# PROJECT-TSC_v61.net
KiCad netlist of a schematic drawn in EAGLE
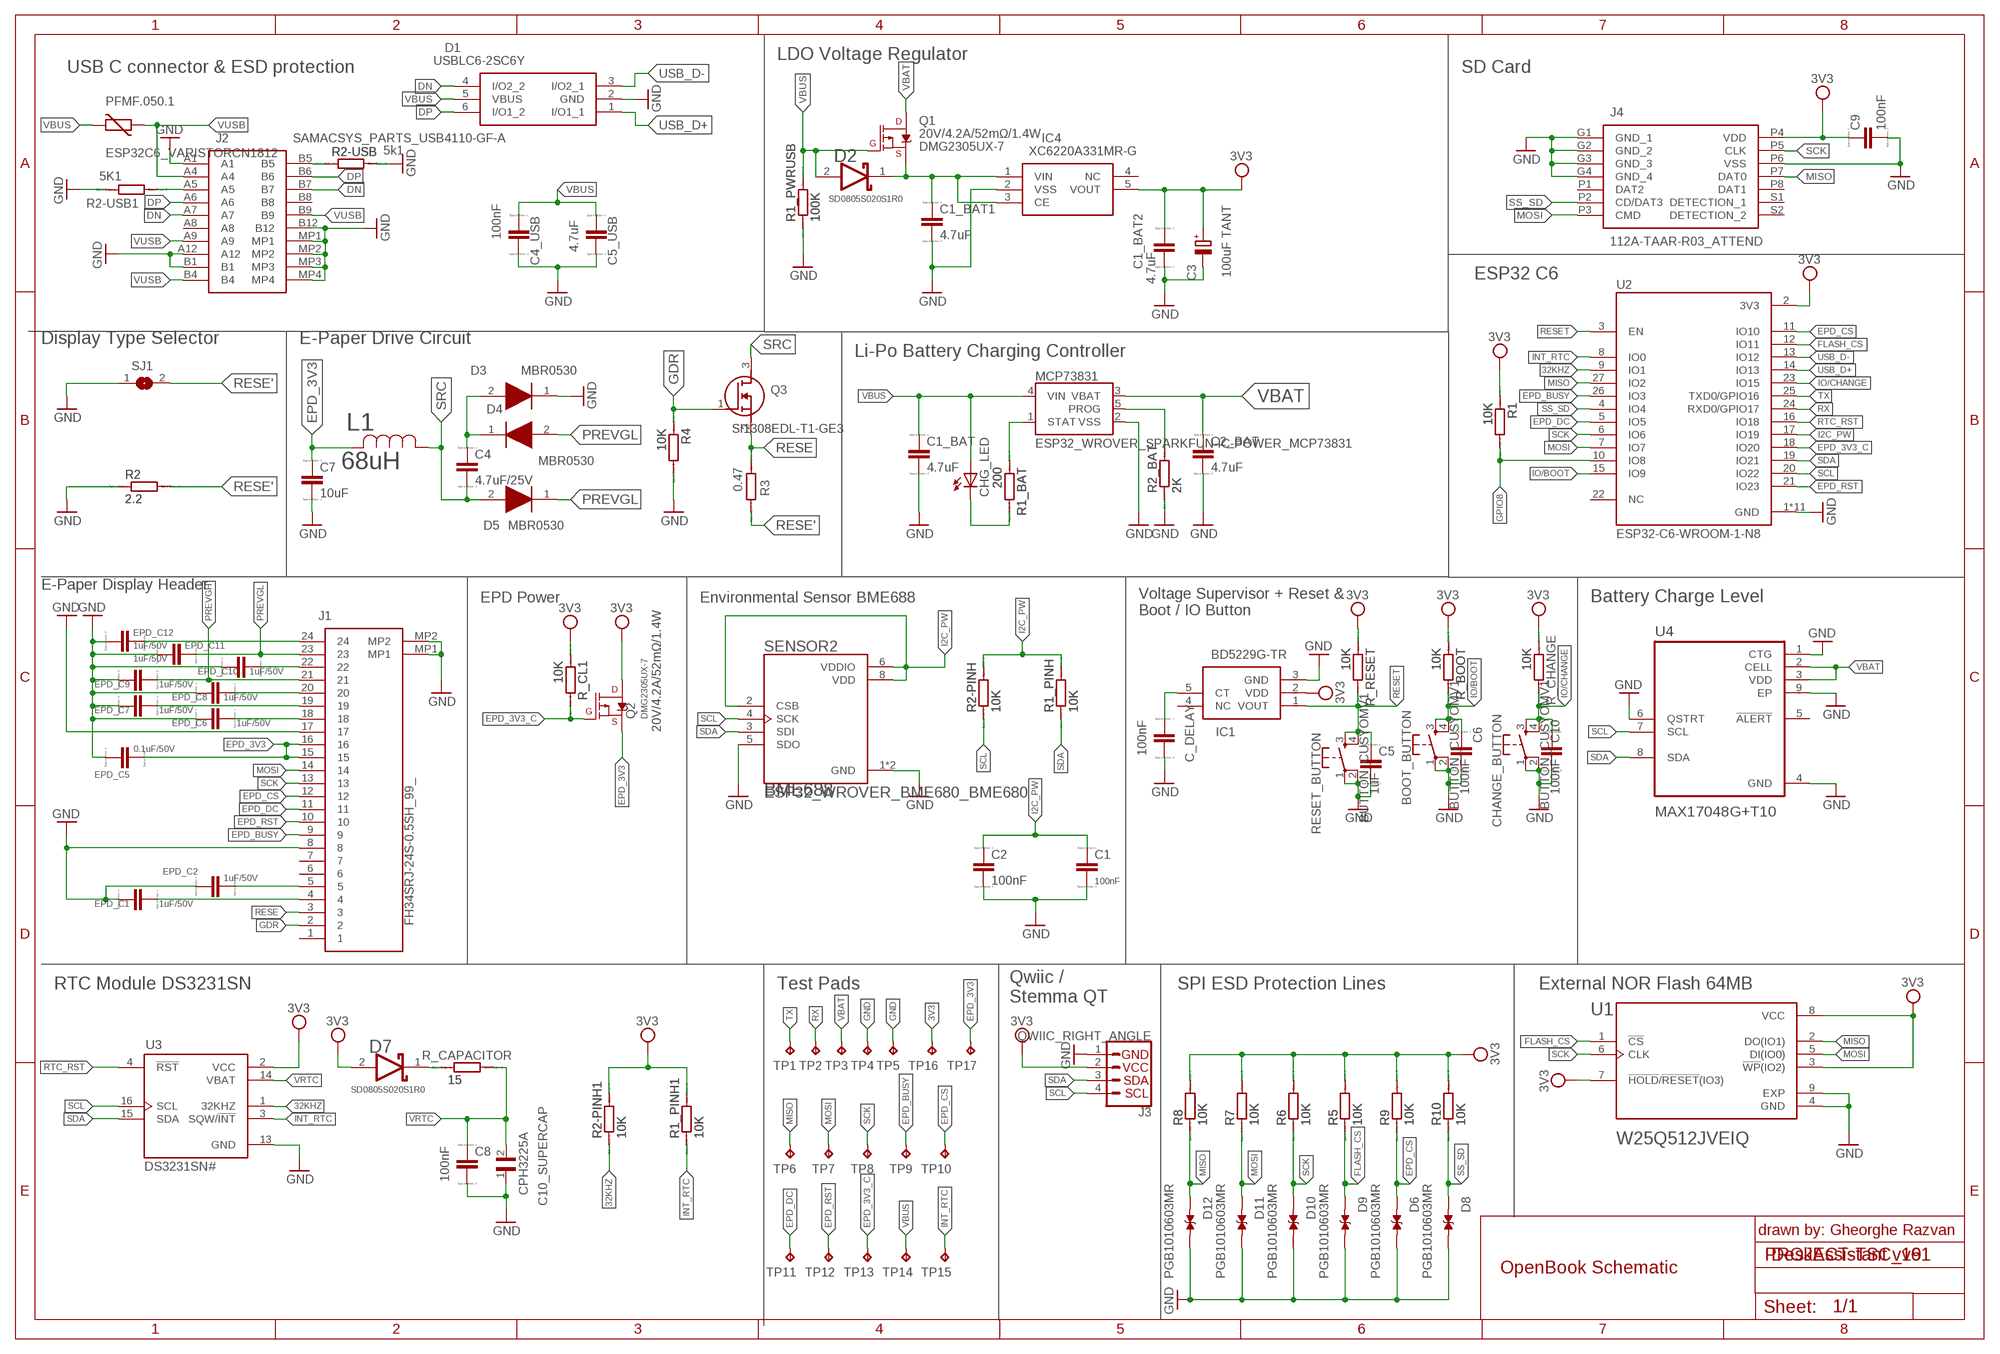
[diagram p0: schematic, sheet 1]

(export (version "E")
  (design (tool "Eeschema 10.0.6"))
  (components
    (comp (ref "BOOT_BUTTON")
      (value "BUTTON_CUSYOMV1")
      (footprint "eagle-import:MYBUTTON")
      (libsource (lib "eagle-import") (part "BUTTON_CUSYOMV1"))
    )
    (comp (ref "C1")
      (value "100nF")
      (footprint "eagle-import:EAGLE-LTSPICE_C0402")
      (libsource (lib "eagle-import") (part "EAGLE-LTSPICE_CC0402"))
    )
    (comp (ref "C1_BAT")
      (value "4.7uF")
      (footprint "eagle-import:EAGLE-LTSPICE_C0402")
      (libsource (lib "eagle-import") (part "ESP32_WROVER_EAGLE-LTSPICE_CC0402"))
    )
    (comp (ref "C1_BAT1")
      (value "4.7uF")
      (footprint "eagle-import:EAGLE-LTSPICE_C0402")
      (libsource (lib "eagle-import") (part "ESP32_WROVER_EAGLE-LTSPICE_CC0402"))
    )
    (comp (ref "C1_BAT2")
      (value "4.7uF")
      (footprint "eagle-import:EAGLE-LTSPICE_C0402")
      (libsource (lib "eagle-import") (part "ESP32_WROVER_EAGLE-LTSPICE_CC0402"))
    )
    (comp (ref "C2")
      (value "100nF")
      (footprint "eagle-import:EAGLE-LTSPICE_C0402")
      (libsource (lib "eagle-import") (part "EAGLE-LTSPICE_CC0402"))
    )
    (comp (ref "C2_BAT")
      (value "4.7uF")
      (footprint "eagle-import:EAGLE-LTSPICE_C0402")
      (libsource (lib "eagle-import") (part "ESP32_WROVER_EAGLE-LTSPICE_CC0402"))
    )
    (comp (ref "C3")
      (value "100uF TANT")
      (footprint "eagle-import:RCL_CT3528")
      (libsource (lib "eagle-import") (part "RCL_CPOL-EUCT3528"))
    )
    (comp (ref "C4")
      (value "4.7uF/25V")
      (footprint "eagle-import:EAGLE-LTSPICE_C0402")
      (libsource (lib "eagle-import") (part "ESP32_WROVER_EAGLE-LTSPICE_CC0402"))
    )
    (comp (ref "C4_USB")
      (value "100nF")
      (footprint "eagle-import:EAGLE-LTSPICE_C0402")
      (libsource (lib "eagle-import") (part "ESP32_WROVER_EAGLE-LTSPICE_CC0402"))
    )
    (comp (ref "C5")
      (value "1uF")
      (footprint "eagle-import:EAGLE-LTSPICE_C0402")
      (libsource (lib "eagle-import") (part "EAGLE-LTSPICE_CC0402"))
    )
    (comp (ref "C5_USB")
      (value "4.7uF")
      (footprint "eagle-import:EAGLE-LTSPICE_C0402")
      (libsource (lib "eagle-import") (part "ESP32_WROVER_EAGLE-LTSPICE_CC0402"))
    )
    (comp (ref "C6")
      (value "100nF")
      (footprint "eagle-import:EAGLE-LTSPICE_C0402")
      (libsource (lib "eagle-import") (part "EAGLE-LTSPICE_CC0402"))
    )
    (comp (ref "C7")
      (value "10uF")
      (footprint "eagle-import:EAGLE-LTSPICE_C0402")
      (libsource (lib "eagle-import") (part "EAGLE-LTSPICE_CC0402"))
    )
    (comp (ref "C8")
      (value "100nF")
      (footprint "eagle-import:EAGLE-LTSPICE_C0402")
      (libsource (lib "eagle-import") (part "ESP32_WROVER_EAGLE-LTSPICE_CC0402"))
    )
    (comp (ref "C9")
      (value "100nF")
      (footprint "eagle-import:EAGLE-LTSPICE_C0402")
      (libsource (lib "eagle-import") (part "ESP32_WROVER_EAGLE-LTSPICE_CC0402"))
    )
    (comp (ref "C10")
      (value "100nF")
      (footprint "eagle-import:EAGLE-LTSPICE_C0402")
      (libsource (lib "eagle-import") (part "EAGLE-LTSPICE_CC0402"))
    )
    (comp (ref "C10_SUPERCAP")
      (value "CPH3225A")
      (footprint "eagle-import:CAPCP3225X100N")
      (fields (field (name "MF") "Seiko Instruments"))
      (libsource (lib "eagle-import") (part "CPH3225A"))
    )
    (comp (ref "CHANGE_BUTTON")
      (value "BUTTON_CUSYOMV1")
      (footprint "eagle-import:MYBUTTON")
      (libsource (lib "eagle-import") (part "BUTTON_CUSYOMV1"))
    )
    (comp (ref "CHG_LED")
      (value "ADAFRUIT_LEDCHIP-LED0603")
      (footprint "eagle-import:ADAFRUIT_CHIP-LED0603")
      (libsource (lib "eagle-import") (part "ADAFRUIT_LEDCHIP-LED0603"))
    )
    (comp (ref "C_DELAY")
      (value "100nF")
      (footprint "eagle-import:EAGLE-LTSPICE_C0402")
      (libsource (lib "eagle-import") (part "EAGLE-LTSPICE_CC0402"))
    )
    (comp (ref "D1")
      (value "USBLC6-2SC6Y")
      (footprint "eagle-import:SOT95P280X145-6N")
      (fields (field (name "MF") "STMicroelectronics"))
      (libsource (lib "eagle-import") (part "USBLC6-2SC6Y"))
    )
    (comp (ref "D2")
      (value "ESP32_WROVER_AVX---SD0805S020S1R0_AVX_SD0805S020S1R0_0_0AVX_SD0805S020S1R0_0_0")
      (footprint "eagle-import:ESP32_WROVER_AVX---SD0805S020S1R0_AVX_SD0805S020S1R0_0")
      (fields
        (field (name "DIGIKEY_PART_NUMBER") "478-7800-1-ND")
        (field (name "MF") "AVX")
        (field (name "MOUSER_PART_NUMBER") "581-SD0805S020S1R0")
      )
      (libsource (lib "eagle-import") (part "ESP32_WROVER_AVX---SD0805S020S1R0_AVX_SD0805S020S1R0_0_0AVX_SD0805S020S1R0_0_0"))
    )
    (comp (ref "D3")
      (value "MBR0530")
      (footprint "eagle-import:SOD3716X135N")
      (fields (field (name "MF") "ON Semiconductor"))
      (libsource (lib "eagle-import") (part "MBR0530"))
    )
    (comp (ref "D4")
      (value "MBR0530")
      (footprint "eagle-import:SOD3716X135N")
      (fields (field (name "MF") "ON Semiconductor"))
      (libsource (lib "eagle-import") (part "MBR0530"))
    )
    (comp (ref "D5")
      (value "MBR0530")
      (footprint "eagle-import:SOD3716X135N")
      (fields (field (name "MF") "ON Semiconductor"))
      (libsource (lib "eagle-import") (part "MBR0530"))
    )
    (comp (ref "D6")
      (value "PGB1010603MR")
      (footprint "eagle-import:DIOC1608X36N")
      (fields (field (name "MF") "Littelfuse Inc."))
      (libsource (lib "eagle-import") (part "PGB1010603MR"))
    )
    (comp (ref "D7")
      (value "ESP32_WROVER_AVX---SD0805S020S1R0_AVX_SD0805S020S1R0_0_0AVX_SD0805S020S1R0_0_0")
      (footprint "eagle-import:ESP32_WROVER_AVX---SD0805S020S1R0_AVX_SD0805S020S1R0_0")
      (fields
        (field (name "DIGIKEY_PART_NUMBER") "478-7800-1-ND")
        (field (name "MF") "AVX")
        (field (name "MOUSER_PART_NUMBER") "581-SD0805S020S1R0")
      )
      (libsource (lib "eagle-import") (part "ESP32_WROVER_AVX---SD0805S020S1R0_AVX_SD0805S020S1R0_0_0AVX_SD0805S020S1R0_0_0"))
    )
    (comp (ref "D8")
      (value "PGB1010603MR")
      (footprint "eagle-import:DIOC1608X36N")
      (fields (field (name "MF") "Littelfuse Inc."))
      (libsource (lib "eagle-import") (part "PGB1010603MR"))
    )
    (comp (ref "D9")
      (value "PGB1010603MR")
      (footprint "eagle-import:DIOC1608X36N")
      (fields (field (name "MF") "Littelfuse Inc."))
      (libsource (lib "eagle-import") (part "PGB1010603MR"))
    )
    (comp (ref "D10")
      (value "PGB1010603MR")
      (footprint "eagle-import:DIOC1608X36N")
      (fields (field (name "MF") "Littelfuse Inc."))
      (libsource (lib "eagle-import") (part "PGB1010603MR"))
    )
    (comp (ref "D11")
      (value "PGB1010603MR")
      (footprint "eagle-import:DIOC1608X36N")
      (fields (field (name "MF") "Littelfuse Inc."))
      (libsource (lib "eagle-import") (part "PGB1010603MR"))
    )
    (comp (ref "D12")
      (value "PGB1010603MR")
      (footprint "eagle-import:DIOC1608X36N")
      (fields (field (name "MF") "Littelfuse Inc."))
      (libsource (lib "eagle-import") (part "PGB1010603MR"))
    )
    (comp (ref "EPD_C1")
      (value "1uF/50V")
      (footprint "eagle-import:EAGLE-LTSPICE_C0402")
      (libsource (lib "eagle-import") (part "ESP32_WROVER_EAGLE-LTSPICE_CC0402"))
    )
    (comp (ref "EPD_C2")
      (value "1uF/50V")
      (footprint "eagle-import:EAGLE-LTSPICE_C0402")
      (libsource (lib "eagle-import") (part "ESP32_WROVER_EAGLE-LTSPICE_CC0402"))
    )
    (comp (ref "EPD_C5")
      (value "0.1uF/50V")
      (footprint "eagle-import:EAGLE-LTSPICE_C0402")
      (libsource (lib "eagle-import") (part "ESP32_WROVER_EAGLE-LTSPICE_CC0402"))
    )
    (comp (ref "EPD_C6")
      (value "1uF/50V")
      (footprint "eagle-import:EAGLE-LTSPICE_C0402")
      (libsource (lib "eagle-import") (part "ESP32_WROVER_EAGLE-LTSPICE_CC0402"))
    )
    (comp (ref "EPD_C7")
      (value "1uF/50V")
      (footprint "eagle-import:EAGLE-LTSPICE_C0402")
      (libsource (lib "eagle-import") (part "ESP32_WROVER_EAGLE-LTSPICE_CC0402"))
    )
    (comp (ref "EPD_C8")
      (value "1uF/50V")
      (footprint "eagle-import:EAGLE-LTSPICE_C0402")
      (libsource (lib "eagle-import") (part "ESP32_WROVER_EAGLE-LTSPICE_CC0402"))
    )
    (comp (ref "EPD_C9")
      (value "1uF/50V")
      (footprint "eagle-import:EAGLE-LTSPICE_C0402")
      (libsource (lib "eagle-import") (part "ESP32_WROVER_EAGLE-LTSPICE_CC0402"))
    )
    (comp (ref "EPD_C10")
      (value "1uF/50V")
      (footprint "eagle-import:EAGLE-LTSPICE_C0402")
      (libsource (lib "eagle-import") (part "ESP32_WROVER_EAGLE-LTSPICE_CC0402"))
    )
    (comp (ref "EPD_C11")
      (value "1uF/50V")
      (footprint "eagle-import:EAGLE-LTSPICE_C0402")
      (libsource (lib "eagle-import") (part "ESP32_WROVER_EAGLE-LTSPICE_CC0402"))
    )
    (comp (ref "EPD_C12")
      (value "1uF/50V")
      (footprint "eagle-import:EAGLE-LTSPICE_C0402")
      (libsource (lib "eagle-import") (part "ESP32_WROVER_EAGLE-LTSPICE_CC0402"))
    )
    (comp (ref "IC1")
      (value "BD5229G-TR")
      (footprint "eagle-import:SOT95P280X120-5N")
      (fields (field (name "MOUSER_PART_NUMBER") "755-BD5229G-TR"))
      (libsource (lib "eagle-import") (part "BD5229G-TR"))
    )
    (comp (ref "IC4")
      (value "XC6220A331MR-G")
      (footprint "eagle-import:SOT95P280X120-5N")
      (fields (field (name "MOUSER_PART_NUMBER") "865-XC6220A331MR-G"))
      (libsource (lib "eagle-import") (part "XC6220A331MR-G"))
    )
    (comp (ref "J1")
      (value "FH34SRJ-24S-0.5SH_99_")
      (footprint "eagle-import:FH34SRJ24S05SH99")
      (fields
        (field (name "MANUFACTURER_PART_NUMBER") "FH34SRJ-24S-0.5SH(99)")
        (field (name "MOUSER_PART_NUMBER") "798-FH34SRJ24S05SH99")
      )
      (libsource (lib "eagle-import") (part "FH34SRJ-24S-0.5SH_99_"))
    )
    (comp (ref "J2")
      (value "SAMACSYS_PARTS_USB4110-GF-A")
      (footprint "eagle-import:SAMACSYS_PARTS_USB4110GFA")
      (fields
        (field (name "MANUFACTURER_PART_NUMBER") "USB4110-GF-A")
        (field (name "MOUSER_PART_NUMBER") "640-USB4110-GF-A")
      )
      (libsource (lib "eagle-import") (part "SAMACSYS_PARTS_USB4110-GF-A"))
    )
    (comp (ref "J3")
      (value "QWIIC_RIGHT_ANGLE")
      (footprint "eagle-import:JST04_1MM_RA")
      (libsource (lib "eagle-import") (part "QWIIC_CONNECTORJS-1MM"))
    )
    (comp (ref "J4")
      (value "112A-TAAR-R03_ATTEND")
      (footprint "eagle-import:112ATAARR03ATTEND")
      (fields (field (name "MANUFACTURER_PART_NUMBER") "112A-TAAR-R03 ATTEND"))
      (libsource (lib "eagle-import") (part "112A-TAAR-R03_ATTEND"))
    )
    (comp (ref "L1")
      (value "68uH")
      (footprint "eagle-import:IND_4828-WE-TPC_WRE")
      (fields
        (field (name "MANUFACTURER_PART_NUMBER") "744043680")
        (field (name "COPYRIGHT") "Copyright (C) 2024 Ultra Librarian. All rights reserved.")
      )
      (libsource (lib "eagle-import") (part "744043680IND_4828-WE-TPC_WRE"))
    )
    (comp (ref "MCP73831")
      (value "ESP32_WROVER_SPARKFUN-IC-POWER_MCP73831")
      (footprint "eagle-import:ESP32_WROVER_SPARKFUN-IC-POWER_SOT23-5")
      (libsource (lib "eagle-import") (part "ESP32_WROVER_SPARKFUN-IC-POWER_MCP73831"))
    )
    (comp (ref "PFMF.050.1")
      (value "ESP32C6_VARISTORCN1812")
      (footprint "eagle-import:ESP32C6_VARISTOR_CT_CN1812")
      (libsource (lib "eagle-import") (part "ESP32C6_VARISTORCN1812"))
    )
    (comp (ref "Q1")
      (value "20V/4.2A/52mΩ/1.4W")
      (footprint "eagle-import:ESP32_WROVER_SPARKFUN-DISCRETESEMI_SOT23-3")
      (libsource (lib "eagle-import") (part "ESP32_WROVER_SPARKFUN-DISCRETESEMI_MOSFET_PCH-DMG2305UX-7"))
    )
    (comp (ref "Q2")
      (value "20V/4.2A/52mΩ/1.4W")
      (footprint "eagle-import:ESP32_WROVER_SPARKFUN-DISCRETESEMI_SOT23-3")
      (libsource (lib "eagle-import") (part "ESP32_WROVER_SPARKFUN-DISCRETESEMI_MOSFET_PCH-DMG2305UX-7"))
    )
    (comp (ref "Q3")
      (value "SI1308EDL-T1-GE3")
      (footprint "eagle-import:SOT65P210X110-3N")
      (fields (field (name "MF") "Vishay Siliconix"))
      (libsource (lib "eagle-import") (part "SI1308EDL-T1-GE3"))
    )
    (comp (ref "R1")
      (value "10K")
      (footprint "eagle-import:ESP32_WROVER_EAGLE-LTSPICE_R0402")
      (libsource (lib "eagle-import") (part "ESP32_WROVER_EAGLE-LTSPICE_RR0402"))
    )
    (comp (ref "R1_BAT")
      (value "200")
      (footprint "eagle-import:ESP32_WROVER_EAGLE-LTSPICE_R0402")
      (libsource (lib "eagle-import") (part "ESP32_WROVER_EAGLE-LTSPICE_RR0402"))
    )
    (comp (ref "R1_PINH")
      (value "10K")
      (footprint "eagle-import:ESP32_WROVER_EAGLE-LTSPICE_R0402")
      (libsource (lib "eagle-import") (part "ESP32_WROVER_EAGLE-LTSPICE_RR0402"))
    )
    (comp (ref "R1_PINH1")
      (value "10K")
      (footprint "eagle-import:ESP32_WROVER_EAGLE-LTSPICE_R0402")
      (libsource (lib "eagle-import") (part "ESP32_WROVER_EAGLE-LTSPICE_RR0402"))
    )
    (comp (ref "R1_PWRUSB")
      (value "100K")
      (footprint "eagle-import:ESP32_WROVER_EAGLE-LTSPICE_R0402")
      (libsource (lib "eagle-import") (part "ESP32_WROVER_EAGLE-LTSPICE_RR0402"))
    )
    (comp (ref "R2")
      (value "2.2")
      (footprint "eagle-import:ESP32_WROVER_EAGLE-LTSPICE_R0402")
      (libsource (lib "eagle-import") (part "ESP32_WROVER_EAGLE-LTSPICE_RR0402"))
    )
    (comp (ref "R2-PINH")
      (value "10K")
      (footprint "eagle-import:ESP32_WROVER_EAGLE-LTSPICE_R0402")
      (libsource (lib "eagle-import") (part "ESP32_WROVER_EAGLE-LTSPICE_RR0402"))
    )
    (comp (ref "R2-PINH1")
      (value "10K")
      (footprint "eagle-import:ESP32_WROVER_EAGLE-LTSPICE_R0402")
      (libsource (lib "eagle-import") (part "ESP32_WROVER_EAGLE-LTSPICE_RR0402"))
    )
    (comp (ref "R2-USB")
      (value "5k1")
      (footprint "eagle-import:ESP32_WROVER_EAGLE-LTSPICE_R0402")
      (libsource (lib "eagle-import") (part "ESP32_WROVER_EAGLE-LTSPICE_RR0402"))
    )
    (comp (ref "R2-USB1")
      (value "5K1")
      (footprint "eagle-import:ESP32_WROVER_EAGLE-LTSPICE_R0402")
      (libsource (lib "eagle-import") (part "ESP32_WROVER_EAGLE-LTSPICE_RR0402"))
    )
    (comp (ref "R2_BAT")
      (value "2K")
      (footprint "eagle-import:ESP32_WROVER_EAGLE-LTSPICE_R0402")
      (libsource (lib "eagle-import") (part "ESP32_WROVER_EAGLE-LTSPICE_RR0402"))
    )
    (comp (ref "R3")
      (value "0.47")
      (footprint "eagle-import:ESP32_WROVER_EAGLE-LTSPICE_R0402")
      (libsource (lib "eagle-import") (part "ESP32_WROVER_EAGLE-LTSPICE_RR0402"))
    )
    (comp (ref "R4")
      (value "10K")
      (footprint "eagle-import:ESP32_WROVER_EAGLE-LTSPICE_R0402")
      (libsource (lib "eagle-import") (part "ESP32_WROVER_EAGLE-LTSPICE_RR0402"))
    )
    (comp (ref "R5")
      (value "10K")
      (footprint "eagle-import:ESP32_WROVER_EAGLE-LTSPICE_R0402")
      (libsource (lib "eagle-import") (part "ESP32_WROVER_EAGLE-LTSPICE_RR0402"))
    )
    (comp (ref "R6")
      (value "10K")
      (footprint "eagle-import:ESP32_WROVER_EAGLE-LTSPICE_R0402")
      (libsource (lib "eagle-import") (part "ESP32_WROVER_EAGLE-LTSPICE_RR0402"))
    )
    (comp (ref "R7")
      (value "10K")
      (footprint "eagle-import:ESP32_WROVER_EAGLE-LTSPICE_R0402")
      (libsource (lib "eagle-import") (part "ESP32_WROVER_EAGLE-LTSPICE_RR0402"))
    )
    (comp (ref "R8")
      (value "10K")
      (footprint "eagle-import:ESP32_WROVER_EAGLE-LTSPICE_R0402")
      (libsource (lib "eagle-import") (part "ESP32_WROVER_EAGLE-LTSPICE_RR0402"))
    )
    (comp (ref "R9")
      (value "10K")
      (footprint "eagle-import:ESP32_WROVER_EAGLE-LTSPICE_R0402")
      (libsource (lib "eagle-import") (part "ESP32_WROVER_EAGLE-LTSPICE_RR0402"))
    )
    (comp (ref "R10")
      (value "10K")
      (footprint "eagle-import:ESP32_WROVER_EAGLE-LTSPICE_R0402")
      (libsource (lib "eagle-import") (part "ESP32_WROVER_EAGLE-LTSPICE_RR0402"))
    )
    (comp (ref "RESET_BUTTON")
      (value "BUTTON_CUSYOMV1")
      (footprint "eagle-import:MYBUTTON")
      (libsource (lib "eagle-import") (part "BUTTON_CUSYOMV1"))
    )
    (comp (ref "R_BOOT")
      (value "10K")
      (footprint "eagle-import:ESP32_WROVER_EAGLE-LTSPICE_R0402")
      (libsource (lib "eagle-import") (part "ESP32_WROVER_EAGLE-LTSPICE_RR0402"))
    )
    (comp (ref "R_CAPACITOR")
      (value "15")
      (footprint "eagle-import:ESP32_WROVER_EAGLE-LTSPICE_R0402")
      (libsource (lib "eagle-import") (part "ESP32_WROVER_EAGLE-LTSPICE_RR0402"))
    )
    (comp (ref "R_CHANGE")
      (value "10K")
      (footprint "eagle-import:ESP32_WROVER_EAGLE-LTSPICE_R0402")
      (libsource (lib "eagle-import") (part "ESP32_WROVER_EAGLE-LTSPICE_RR0402"))
    )
    (comp (ref "R_CL1")
      (value "10K")
      (footprint "eagle-import:ESP32_WROVER_EAGLE-LTSPICE_R0402")
      (libsource (lib "eagle-import") (part "ESP32_WROVER_EAGLE-LTSPICE_RR0402"))
    )
    (comp (ref "R_RESET")
      (value "10K")
      (footprint "eagle-import:ESP32_WROVER_EAGLE-LTSPICE_R0402")
      (libsource (lib "eagle-import") (part "ESP32_WROVER_EAGLE-LTSPICE_RR0402"))
    )
    (comp (ref "SENSOR2")
      (value "ESP32_WROVER_BME680_BME680")
      (footprint "eagle-import:ESP32_WROVER_BME680_PSON80P300X300X100-8N")
      (fields (field (name "MF") "Bosch Sensortec") (field (name "MP") "BME680"))
      (libsource (lib "eagle-import") (part "ESP32_WROVER_BME680_BME680"))
    )
    (comp (ref "SJ1") (value "SJ") (footprint "eagle-import:SJ") (libsource (lib "eagle-import") (part "SJ")))
    (comp (ref "TP1")
      (value "TPTP20R")
      (footprint "eagle-import:TP20R")
      (libsource (lib "eagle-import") (part "TPTP20R"))
    )
    (comp (ref "TP2")
      (value "TPTP20R")
      (footprint "eagle-import:TP20R")
      (libsource (lib "eagle-import") (part "TPTP20R"))
    )
    (comp (ref "TP3")
      (value "TPTP20R")
      (footprint "eagle-import:TP20R")
      (libsource (lib "eagle-import") (part "TPTP20R"))
    )
    (comp (ref "TP4")
      (value "TPTP20R")
      (footprint "eagle-import:TP20R")
      (libsource (lib "eagle-import") (part "TPTP20R"))
    )
    (comp (ref "TP5")
      (value "TPTP20R")
      (footprint "eagle-import:TP20R")
      (libsource (lib "eagle-import") (part "TPTP20R"))
    )
    (comp (ref "TP6")
      (value "TPTP20R")
      (footprint "eagle-import:TP20R")
      (libsource (lib "eagle-import") (part "TPTP20R"))
    )
    (comp (ref "TP7")
      (value "TPTP20R")
      (footprint "eagle-import:TP20R")
      (libsource (lib "eagle-import") (part "TPTP20R"))
    )
    (comp (ref "TP8")
      (value "TPTP20R")
      (footprint "eagle-import:TP20R")
      (libsource (lib "eagle-import") (part "TPTP20R"))
    )
    (comp (ref "TP9")
      (value "TPTP20R")
      (footprint "eagle-import:TP20R")
      (libsource (lib "eagle-import") (part "TPTP20R"))
    )
    (comp (ref "TP10")
      (value "TPTP20R")
      (footprint "eagle-import:TP20R")
      (libsource (lib "eagle-import") (part "TPTP20R"))
    )
    (comp (ref "TP11")
      (value "TPTP20R")
      (footprint "eagle-import:TP20R")
      (libsource (lib "eagle-import") (part "TPTP20R"))
    )
    (comp (ref "TP12")
      (value "TPTP20R")
      (footprint "eagle-import:TP20R")
      (libsource (lib "eagle-import") (part "TPTP20R"))
    )
    (comp (ref "TP13")
      (value "TPTP20R")
      (footprint "eagle-import:TP20R")
      (libsource (lib "eagle-import") (part "TPTP20R"))
    )
    (comp (ref "TP14")
      (value "TPTP20R")
      (footprint "eagle-import:TP20R")
      (libsource (lib "eagle-import") (part "TPTP20R"))
    )
    (comp (ref "TP15")
      (value "TPTP20R")
      (footprint "eagle-import:TP20R")
      (libsource (lib "eagle-import") (part "TPTP20R"))
    )
    (comp (ref "TP16")
      (value "TPTP20R")
      (footprint "eagle-import:TP20R")
      (libsource (lib "eagle-import") (part "TPTP20R"))
    )
    (comp (ref "TP17")
      (value "TPTP20R")
      (footprint "eagle-import:TP20R")
      (libsource (lib "eagle-import") (part "TPTP20R"))
    )
    (comp (ref "U1")
      (value "W25Q512JVEIQ")
      (footprint "eagle-import:SON127P600X800X80-9N")
      (fields (field (name "MF") "Winbond Electronics"))
      (libsource (lib "eagle-import") (part "W25Q512JVEIQ"))
    )
    (comp (ref "U2")
      (value "ESP32-C6-WROOM-1-N8")
      (footprint "eagle-import:XCVR_ESP32-C6-WROOM-1-N8")
      (fields (field (name "MF") "Espressif Systems"))
      (libsource (lib "eagle-import") (part "ESP32-C6-WROOM-1-N8"))
    )
    (comp (ref "U3")
      (value "DS3231SN#")
      (footprint "eagle-import:SOIC127P1032X265-16N")
      (fields (field (name "MF") "Analog Devices"))
      (libsource (lib "eagle-import") (part "DS3231SN#"))
    )
    (comp (ref "U4")
      (value "MAX17048G+T10")
      (footprint "eagle-import:SON50P200X200X80-9N")
      (fields (field (name "MF") "Analog Devices"))
      (libsource (lib "eagle-import") (part "MAX17048G+T10"))
    )
  )
  (nets
    (net (code "1") (name "3V3") (class "Default")
      (node (ref "C1_BAT2") (pin "1") (pinfunction "1_1") (pintype "passive"))
      (node (ref "C3") (pin "+") (pinfunction "+_+") (pintype "passive"))
      (node (ref "C9") (pin "1") (pinfunction "1_1") (pintype "passive"))
      (node (ref "D7") (pin "2") (pinfunction "ANODE_2") (pintype "bidirectional"))
      (node (ref "IC1") (pin "2") (pinfunction "VDD_2") (pintype "bidirectional"))
      (node (ref "IC4") (pin "5") (pinfunction "VOUT_5") (pintype "bidirectional"))
      (node (ref "J3") (pin "2") (pinfunction "2_2") (pintype "power_in"))
      (node (ref "J4") (pin "P4") (pinfunction "VDD_P4") (pintype "bidirectional"))
      (node (ref "Q2") (pin "3") (pinfunction "D_3") (pintype "bidirectional"))
      (node (ref "R1") (pin "1") (pinfunction "1_1") (pintype "passive"))
      (node (ref "R10") (pin "2") (pinfunction "2_2") (pintype "passive"))
      (node (ref "R1_PINH1") (pin "2") (pinfunction "2_2") (pintype "passive"))
      (node (ref "R2-PINH1") (pin "2") (pinfunction "2_2") (pintype "passive"))
      (node (ref "R5") (pin "2") (pinfunction "2_2") (pintype "passive"))
      (node (ref "R6") (pin "2") (pinfunction "2_2") (pintype "passive"))
      (node (ref "R7") (pin "2") (pinfunction "2_2") (pintype "passive"))
      (node (ref "R8") (pin "2") (pinfunction "2_2") (pintype "passive"))
      (node (ref "R9") (pin "2") (pinfunction "2_2") (pintype "passive"))
      (node (ref "R_BOOT") (pin "1") (pinfunction "1_1") (pintype "passive"))
      (node (ref "R_CHANGE") (pin "1") (pinfunction "1_1") (pintype "passive"))
      (node (ref "R_CL1") (pin "1") (pinfunction "1_1") (pintype "passive"))
      (node (ref "R_RESET") (pin "1") (pinfunction "1_1") (pintype "passive"))
      (node (ref "TP16") (pin "TP") (pinfunction "TP_TP") (pintype "input"))
      (node (ref "U1") (pin "3") (pinfunction "~{WP}(IO2)_3") (pintype "bidirectional"))
      (node (ref "U1") (pin "7") (pinfunction "~{HOLD}/~{RESET}(IO3)_7") (pintype "bidirectional"))
      (node (ref "U1") (pin "8") (pinfunction "VCC_8") (pintype "power_in"))
      (node (ref "U2") (pin "2") (pinfunction "3V3_2") (pintype "power_in"))
      (node (ref "U3") (pin "2") (pinfunction "VCC_2") (pintype "power_in"))
    )
    (net (code "2") (name "32KHZ") (class "Default")
      (node (ref "R2-PINH1") (pin "1") (pinfunction "1_1") (pintype "passive"))
      (node (ref "U2") (pin "9") (pinfunction "IO1_9") (pintype "bidirectional"))
      (node (ref "U3") (pin "1") (pinfunction "32KHZ_1") (pintype "output"))
    )
    (net (code "3") (name "DN") (class "Default")
      (node (ref "D1") (pin "4") (pinfunction "I/O2_2_4") (pintype "bidirectional"))
      (node (ref "J2") (pin "A7") (pinfunction "A7_A7") (pintype "bidirectional"))
      (node (ref "J2") (pin "B7") (pinfunction "B7_B7") (pintype "bidirectional"))
    )
    (net (code "4") (name "DP") (class "Default")
      (node (ref "D1") (pin "6") (pinfunction "I/O1_2_6") (pintype "bidirectional"))
      (node (ref "J2") (pin "A6") (pinfunction "A6_A6") (pintype "bidirectional"))
      (node (ref "J2") (pin "B6") (pinfunction "B6_B6") (pintype "bidirectional"))
    )
    (net (code "5") (name "EPD_3V3") (class "Default")
      (node (ref "C7") (pin "1") (pinfunction "1_1") (pintype "passive"))
      (node (ref "EPD_C5") (pin "1") (pinfunction "1_1") (pintype "passive"))
      (node (ref "J1") (pin "15") (pinfunction "15_15") (pintype "bidirectional"))
      (node (ref "J1") (pin "16") (pinfunction "16_16") (pintype "bidirectional"))
      (node (ref "L1") (pin "2") (pinfunction "2_2") (pintype "passive"))
      (node (ref "Q2") (pin "2") (pinfunction "S_2") (pintype "bidirectional"))
      (node (ref "TP17") (pin "TP") (pinfunction "TP_TP") (pintype "input"))
    )
    (net (code "6") (name "EPD_3V3_C") (class "Default")
      (node (ref "Q2") (pin "1") (pinfunction "G_1") (pintype "bidirectional"))
      (node (ref "R_CL1") (pin "2") (pinfunction "2_2") (pintype "passive"))
      (node (ref "TP13") (pin "TP") (pinfunction "TP_TP") (pintype "input"))
      (node (ref "U2") (pin "18") (pinfunction "IO20_18") (pintype "bidirectional"))
    )
    (net (code "7") (name "EPD_BUSY") (class "Default")
      (node (ref "J1") (pin "9") (pinfunction "9_9") (pintype "bidirectional"))
      (node (ref "TP9") (pin "TP") (pinfunction "TP_TP") (pintype "input"))
      (node (ref "U2") (pin "26") (pinfunction "IO3_26") (pintype "bidirectional"))
    )
    (net (code "8") (name "EPD_CS") (class "Default")
      (node (ref "D6") (pin "1") (pinfunction "1_1") (pintype "passive"))
      (node (ref "J1") (pin "12") (pinfunction "12_12") (pintype "bidirectional"))
      (node (ref "R9") (pin "1") (pinfunction "1_1") (pintype "passive"))
      (node (ref "TP10") (pin "TP") (pinfunction "TP_TP") (pintype "input"))
      (node (ref "U2") (pin "11") (pinfunction "IO10_11") (pintype "bidirectional"))
    )
    (net (code "9") (name "EPD_DC") (class "Default")
      (node (ref "J1") (pin "11") (pinfunction "11_11") (pintype "bidirectional"))
      (node (ref "TP11") (pin "TP") (pinfunction "TP_TP") (pintype "input"))
      (node (ref "U2") (pin "5") (pinfunction "IO5_5") (pintype "bidirectional"))
    )
    (net (code "10") (name "EPD_RST") (class "Default")
      (node (ref "J1") (pin "10") (pinfunction "10_10") (pintype "bidirectional"))
      (node (ref "TP12") (pin "TP") (pinfunction "TP_TP") (pintype "input"))
      (node (ref "U2") (pin "21") (pinfunction "IO23_21") (pintype "bidirectional"))
    )
    (net (code "11") (name "FLASH_CS") (class "Default")
      (node (ref "D9") (pin "1") (pinfunction "1_1") (pintype "passive"))
      (node (ref "R5") (pin "1") (pinfunction "1_1") (pintype "passive"))
      (node (ref "U1") (pin "1") (pinfunction "~{CS}_1") (pintype "input"))
      (node (ref "U2") (pin "12") (pinfunction "IO11_12") (pintype "bidirectional"))
    )
    (net (code "12") (name "GDR") (class "Default")
      (node (ref "J1") (pin "2") (pinfunction "2_2") (pintype "bidirectional"))
      (node (ref "Q3") (pin "1") (pinfunction "G_1") (pintype "bidirectional"))
      (node (ref "R4") (pin "1") (pinfunction "1_1") (pintype "passive"))
    )
    (net (code "13") (name "GND") (class "Default")
      (node (ref "BOOT_BUTTON") (pin "1") (pinfunction "1_1") (pintype "passive"))
      (node (ref "BOOT_BUTTON") (pin "2") (pinfunction "2_2") (pintype "passive"))
      (node (ref "C1") (pin "2") (pinfunction "2_2") (pintype "passive"))
      (node (ref "C10") (pin "2") (pinfunction "2_2") (pintype "passive"))
      (node (ref "C10_SUPERCAP") (pin "1") (pinfunction "1_1") (pintype "passive"))
      (node (ref "C1_BAT") (pin "2") (pinfunction "2_2") (pintype "passive"))
      (node (ref "C1_BAT1") (pin "2") (pinfunction "2_2") (pintype "passive"))
      (node (ref "C1_BAT2") (pin "2") (pinfunction "2_2") (pintype "passive"))
      (node (ref "C2") (pin "2") (pinfunction "2_2") (pintype "passive"))
      (node (ref "C2_BAT") (pin "2") (pinfunction "2_2") (pintype "passive"))
      (node (ref "C3") (pin "-") (pinfunction "-_-") (pintype "passive"))
      (node (ref "C4_USB") (pin "2") (pinfunction "2_2") (pintype "passive"))
      (node (ref "C5") (pin "2") (pinfunction "2_2") (pintype "passive"))
      (node (ref "C5_USB") (pin "2") (pinfunction "2_2") (pintype "passive"))
      (node (ref "C6") (pin "2") (pinfunction "2_2") (pintype "passive"))
      (node (ref "C7") (pin "2") (pinfunction "2_2") (pintype "passive"))
      (node (ref "C8") (pin "2") (pinfunction "2_2") (pintype "passive"))
      (node (ref "C9") (pin "2") (pinfunction "2_2") (pintype "passive"))
      (node (ref "CHANGE_BUTTON") (pin "1") (pinfunction "1_1") (pintype "passive"))
      (node (ref "CHANGE_BUTTON") (pin "2") (pinfunction "2_2") (pintype "passive"))
      (node (ref "C_DELAY") (pin "2") (pinfunction "2_2") (pintype "passive"))
      (node (ref "D1") (pin "2") (pinfunction "GND_2") (pintype "bidirectional"))
      (node (ref "D10") (pin "2") (pinfunction "2_2") (pintype "passive"))
      (node (ref "D11") (pin "2") (pinfunction "2_2") (pintype "passive"))
      (node (ref "D12") (pin "2") (pinfunction "2_2") (pintype "passive"))
      (node (ref "D3") (pin "1") (pinfunction "K_1") (pintype "bidirectional"))
      (node (ref "D6") (pin "2") (pinfunction "2_2") (pintype "passive"))
      (node (ref "D8") (pin "2") (pinfunction "2_2") (pintype "passive"))
      (node (ref "D9") (pin "2") (pinfunction "2_2") (pintype "passive"))
      (node (ref "EPD_C1") (pin "2") (pinfunction "2_2") (pintype "passive"))
      (node (ref "EPD_C10") (pin "2") (pinfunction "2_2") (pintype "passive"))
      (node (ref "EPD_C11") (pin "2") (pinfunction "2_2") (pintype "passive"))
      (node (ref "EPD_C12") (pin "2") (pinfunction "2_2") (pintype "passive"))
      (node (ref "EPD_C2") (pin "2") (pinfunction "2_2") (pintype "passive"))
      (node (ref "EPD_C5") (pin "2") (pinfunction "2_2") (pintype "passive"))
      (node (ref "EPD_C6") (pin "2") (pinfunction "2_2") (pintype "passive"))
      (node (ref "EPD_C7") (pin "2") (pinfunction "2_2") (pintype "passive"))
      (node (ref "EPD_C8") (pin "2") (pinfunction "2_2") (pintype "passive"))
      (node (ref "EPD_C9") (pin "2") (pinfunction "2_2") (pintype "passive"))
      (node (ref "IC1") (pin "3") (pinfunction "GND_3") (pintype "bidirectional"))
      (node (ref "IC4") (pin "2") (pinfunction "VSS_2") (pintype "bidirectional"))
      (node (ref "J1") (pin "17") (pinfunction "17_17") (pintype "bidirectional"))
      (node (ref "J1") (pin "8") (pinfunction "8_8") (pintype "bidirectional"))
      (node (ref "J1") (pin "MP1") (pinfunction "MP1_MP1") (pintype "bidirectional"))
      (node (ref "J1") (pin "MP2") (pinfunction "MP2_MP2") (pintype "bidirectional"))
      (node (ref "J2") (pin "A1") (pinfunction "A1_A1") (pintype "bidirectional"))
      (node (ref "J2") (pin "A12") (pinfunction "A12_A12") (pintype "bidirectional"))
      (node (ref "J2") (pin "B1") (pinfunction "B1_B1") (pintype "bidirectional"))
      (node (ref "J2") (pin "B12") (pinfunction "B12_B12") (pintype "bidirectional"))
      (node (ref "J2") (pin "MP1") (pinfunction "MP1_MP1") (pintype "bidirectional"))
      (node (ref "J2") (pin "MP2") (pinfunction "MP2_MP2") (pintype "bidirectional"))
      (node (ref "J2") (pin "MP3") (pinfunction "MP3_MP3") (pintype "bidirectional"))
      (node (ref "J2") (pin "MP4") (pinfunction "MP4_MP4") (pintype "bidirectional"))
      (node (ref "J3") (pin "1") (pinfunction "1_1") (pintype "power_in"))
      (node (ref "J4") (pin "G1") (pinfunction "GND_1_G1") (pintype "bidirectional"))
      (node (ref "J4") (pin "G2") (pinfunction "GND_2_G2") (pintype "bidirectional"))
      (node (ref "J4") (pin "G3") (pinfunction "GND_3_G3") (pintype "bidirectional"))
      (node (ref "J4") (pin "G4") (pinfunction "GND_4_G4") (pintype "bidirectional"))
      (node (ref "J4") (pin "P6") (pinfunction "VSS_P6") (pintype "bidirectional"))
      (node (ref "MCP73831") (pin "2") (pinfunction "VSS_2") (pintype "power_in"))
      (node (ref "R1_PWRUSB") (pin "1") (pinfunction "1_1") (pintype "passive"))
      (node (ref "R2") (pin "1") (pinfunction "1_1") (pintype "passive"))
      (node (ref "R2-USB") (pin "2") (pinfunction "2_2") (pintype "passive"))
      (node (ref "R2-USB1") (pin "1") (pinfunction "1_1") (pintype "passive"))
      (node (ref "R2_BAT") (pin "1") (pinfunction "1_1") (pintype "passive"))
      (node (ref "R4") (pin "2") (pinfunction "2_2") (pintype "passive"))
      (node (ref "RESET_BUTTON") (pin "1") (pinfunction "1_1") (pintype "passive"))
      (node (ref "RESET_BUTTON") (pin "2") (pinfunction "2_2") (pintype "passive"))
      (node (ref "SENSOR2") (pin "1") (pinfunction "GND_1") (pintype "power_in"))
      (node (ref "SENSOR2") (pin "5") (pinfunction "SDO_5") (pintype "bidirectional"))
      (node (ref "SENSOR2") (pin "7") (pinfunction "GND_7") (pintype "power_in"))
      (node (ref "SJ1") (pin "1") (pinfunction "1_1") (pintype "passive"))
      (node (ref "TP4") (pin "TP") (pinfunction "TP_TP") (pintype "input"))
      (node (ref "TP5") (pin "TP") (pinfunction "TP_TP") (pintype "input"))
      (node (ref "U1") (pin "4") (pinfunction "GND_4") (pintype "power_in"))
      (node (ref "U1") (pin "9") (pinfunction "EXP_9") (pintype "passive"))
      (node (ref "U2") (pin "1") (pinfunction "GND_1") (pintype "power_in"))
      (node (ref "U2") (pin "28") (pinfunction "GND_28") (pintype "power_in"))
      (node (ref "U2") (pin "29_1") (pinfunction "GND_29_1") (pintype "power_in"))
      (node (ref "U2") (pin "29_2") (pinfunction "GND_29_2") (pintype "power_in"))
      (node (ref "U2") (pin "29_3") (pinfunction "GND_29_3") (pintype "power_in"))
      (node (ref "U2") (pin "29_4") (pinfunction "GND_29_4") (pintype "power_in"))
      (node (ref "U2") (pin "29_5") (pinfunction "GND_29_5") (pintype "power_in"))
      (node (ref "U2") (pin "29_6") (pinfunction "GND_29_6") (pintype "power_in"))
      (node (ref "U2") (pin "29_7") (pinfunction "GND_29_7") (pintype "power_in"))
      (node (ref "U2") (pin "29_8") (pinfunction "GND_29_8") (pintype "power_in"))
      (node (ref "U2") (pin "29_9") (pinfunction "GND_29_9") (pintype "power_in"))
      (node (ref "U3") (pin "13") (pinfunction "GND_13") (pintype "power_in"))
      (node (ref "U4") (pin "1") (pinfunction "CTG_1") (pintype "power_in"))
      (node (ref "U4") (pin "4") (pinfunction "GND_4") (pintype "power_in"))
      (node (ref "U4") (pin "6") (pinfunction "QSTRT_6") (pintype "input"))
      (node (ref "U4") (pin "9") (pinfunction "EP_9") (pintype "power_in"))
    )
    (net (code "14") (name "GPIO8") (class "Default")
      (node (ref "R1") (pin "2") (pinfunction "2_2") (pintype "passive"))
      (node (ref "U2") (pin "10") (pinfunction "IO8_10") (pintype "bidirectional"))
    )
    (net (code "15") (name "I2C_PW") (class "Default")
      (node (ref "C1") (pin "1") (pinfunction "1_1") (pintype "passive"))
      (node (ref "C2") (pin "1") (pinfunction "1_1") (pintype "passive"))
      (node (ref "R1_PINH") (pin "2") (pinfunction "2_2") (pintype "passive"))
      (node (ref "R2-PINH") (pin "2") (pinfunction "2_2") (pintype "passive"))
      (node (ref "SENSOR2") (pin "2") (pinfunction "CSB_2") (pintype "input"))
      (node (ref "SENSOR2") (pin "6") (pinfunction "VDDIO_6") (pintype "power_in"))
      (node (ref "SENSOR2") (pin "8") (pinfunction "VDD_8") (pintype "power_in"))
      (node (ref "U2") (pin "17") (pinfunction "IO19_17") (pintype "bidirectional"))
    )
    (net (code "16") (name "INT_RTC") (class "Default")
      (node (ref "R1_PINH1") (pin "1") (pinfunction "1_1") (pintype "passive"))
      (node (ref "TP15") (pin "TP") (pinfunction "TP_TP") (pintype "input"))
      (node (ref "U2") (pin "8") (pinfunction "IO0_8") (pintype "bidirectional"))
      (node (ref "U3") (pin "3") (pinfunction "SQW/~{INT}_3") (pintype "output"))
    )
    (net (code "17") (name "IO{slash}BOOT") (class "Default")
      (node (ref "BOOT_BUTTON") (pin "3") (pinfunction "3_3") (pintype "passive"))
      (node (ref "BOOT_BUTTON") (pin "4") (pinfunction "4_4") (pintype "passive"))
      (node (ref "C6") (pin "1") (pinfunction "1_1") (pintype "passive"))
      (node (ref "R_BOOT") (pin "2") (pinfunction "2_2") (pintype "passive"))
      (node (ref "U2") (pin "15") (pinfunction "IO9_15") (pintype "bidirectional"))
    )
    (net (code "18") (name "IO{slash}CHANGE") (class "Default")
      (node (ref "C10") (pin "1") (pinfunction "1_1") (pintype "passive"))
      (node (ref "CHANGE_BUTTON") (pin "3") (pinfunction "3_3") (pintype "passive"))
      (node (ref "CHANGE_BUTTON") (pin "4") (pinfunction "4_4") (pintype "passive"))
      (node (ref "R_CHANGE") (pin "2") (pinfunction "2_2") (pintype "passive"))
      (node (ref "U2") (pin "23") (pinfunction "IO15_23") (pintype "bidirectional"))
    )
    (net (code "19") (name "MISO") (class "Default")
      (node (ref "D12") (pin "1") (pinfunction "1_1") (pintype "passive"))
      (node (ref "J4") (pin "P7") (pinfunction "DAT0_P7") (pintype "bidirectional"))
      (node (ref "R8") (pin "1") (pinfunction "1_1") (pintype "passive"))
      (node (ref "TP6") (pin "TP") (pinfunction "TP_TP") (pintype "input"))
      (node (ref "U1") (pin "2") (pinfunction "DO(IO1)_2") (pintype "bidirectional"))
      (node (ref "U2") (pin "27") (pinfunction "IO2_27") (pintype "bidirectional"))
    )
    (net (code "20") (name "MOSI") (class "Default")
      (node (ref "D11") (pin "1") (pinfunction "1_1") (pintype "passive"))
      (node (ref "J1") (pin "14") (pinfunction "14_14") (pintype "bidirectional"))
      (node (ref "J4") (pin "P3") (pinfunction "CMD_P3") (pintype "bidirectional"))
      (node (ref "R7") (pin "1") (pinfunction "1_1") (pintype "passive"))
      (node (ref "TP7") (pin "TP") (pinfunction "TP_TP") (pintype "input"))
      (node (ref "U1") (pin "5") (pinfunction "DI(IO0)_5") (pintype "bidirectional"))
      (node (ref "U2") (pin "7") (pinfunction "IO7_7") (pintype "bidirectional"))
    )
    (net (code "21") (name "Net-(CHG_LED-PadC)") (class "Default")
      (node (ref "CHG_LED") (pin "C") (pinfunction "C_C") (pintype "passive"))
      (node (ref "R1_BAT") (pin "2") (pinfunction "2_2") (pintype "passive"))
    )
    (net (code "22") (name "Net-(D2-CATHODE)") (class "Default")
      (node (ref "C1_BAT1") (pin "1") (pinfunction "1_1") (pintype "passive"))
      (node (ref "D2") (pin "1") (pinfunction "CATHODE_1") (pintype "bidirectional"))
      (node (ref "IC4") (pin "1") (pinfunction "VIN_1") (pintype "bidirectional"))
      (node (ref "IC4") (pin "3") (pinfunction "CE_3") (pintype "bidirectional"))
      (node (ref "Q1") (pin "2") (pinfunction "S_2") (pintype "bidirectional"))
    )
    (net (code "23") (name "Net-(D3-A)") (class "Default")
      (node (ref "C4") (pin "1") (pinfunction "1_1") (pintype "passive"))
      (node (ref "D3") (pin "2") (pinfunction "A_2") (pintype "bidirectional"))
      (node (ref "D4") (pin "1") (pinfunction "K_1") (pintype "bidirectional"))
    )
    (net (code "24") (name "Net-(D7-CATHODE)") (class "Default")
      (node (ref "D7") (pin "1") (pinfunction "CATHODE_1") (pintype "bidirectional"))
      (node (ref "R_CAPACITOR") (pin "1") (pinfunction "1_1") (pintype "passive"))
    )
    (net (code "25") (name "Net-(EPD_C1-Pad1)") (class "Default")
      (node (ref "EPD_C1") (pin "1") (pinfunction "1_1") (pintype "passive"))
      (node (ref "J1") (pin "4") (pinfunction "4_4") (pintype "bidirectional"))
    )
    (net (code "26") (name "Net-(EPD_C2-Pad1)") (class "Default")
      (node (ref "EPD_C2") (pin "1") (pinfunction "1_1") (pintype "passive"))
      (node (ref "J1") (pin "5") (pinfunction "5_5") (pintype "bidirectional"))
    )
    (net (code "27") (name "Net-(EPD_C6-Pad1)") (class "Default")
      (node (ref "EPD_C6") (pin "1") (pinfunction "1_1") (pintype "passive"))
      (node (ref "J1") (pin "18") (pinfunction "18_18") (pintype "bidirectional"))
    )
    (net (code "28") (name "Net-(EPD_C7-Pad1)") (class "Default")
      (node (ref "EPD_C7") (pin "1") (pinfunction "1_1") (pintype "passive"))
      (node (ref "J1") (pin "19") (pinfunction "19_19") (pintype "bidirectional"))
    )
    (net (code "29") (name "Net-(EPD_C8-Pad1)") (class "Default")
      (node (ref "EPD_C8") (pin "1") (pinfunction "1_1") (pintype "passive"))
      (node (ref "J1") (pin "20") (pinfunction "20_20") (pintype "bidirectional"))
    )
    (net (code "30") (name "Net-(EPD_C10-Pad1)") (class "Default")
      (node (ref "EPD_C10") (pin "1") (pinfunction "1_1") (pintype "passive"))
      (node (ref "J1") (pin "22") (pinfunction "22_22") (pintype "bidirectional"))
    )
    (net (code "31") (name "Net-(EPD_C12-Pad1)") (class "Default")
      (node (ref "EPD_C12") (pin "1") (pinfunction "1_1") (pintype "passive"))
      (node (ref "J1") (pin "24") (pinfunction "24_24") (pintype "bidirectional"))
    )
    (net (code "32") (name "Net-(IC1-CT)") (class "Default")
      (node (ref "C_DELAY") (pin "1") (pinfunction "1_1") (pintype "passive"))
      (node (ref "IC1") (pin "5") (pinfunction "CT_5") (pintype "bidirectional"))
    )
    (net (code "33") (name "Net-(J2-PadA5)") (class "Default")
      (node (ref "J2") (pin "A5") (pinfunction "A5_A5") (pintype "bidirectional"))
      (node (ref "R2-USB1") (pin "2") (pinfunction "2_2") (pintype "passive"))
    )
    (net (code "34") (name "Net-(J2-PadB5)") (class "Default")
      (node (ref "J2") (pin "B5") (pinfunction "B5_B5") (pintype "bidirectional"))
      (node (ref "R2-USB") (pin "1") (pinfunction "1_1") (pintype "passive"))
    )
    (net (code "35") (name "Net-(MCP73831-PROG)") (class "Default")
      (node (ref "MCP73831") (pin "5") (pinfunction "PROG_5") (pintype "input"))
      (node (ref "R2_BAT") (pin "2") (pinfunction "2_2") (pintype "passive"))
    )
    (net (code "36") (name "Net-(MCP73831-STAT)") (class "Default")
      (node (ref "MCP73831") (pin "1") (pinfunction "STAT_1") (pintype "output"))
      (node (ref "R1_BAT") (pin "1") (pinfunction "1_1") (pintype "passive"))
    )
    (net (code "37") (name "PREVGH") (class "Default")
      (node (ref "EPD_C9") (pin "1") (pinfunction "1_1") (pintype "passive"))
      (node (ref "J1") (pin "21") (pinfunction "21_21") (pintype "bidirectional"))
    )
    (net (code "38") (name "PREVGL") (class "Default")
      (node (ref "D4") (pin "2") (pinfunction "A_2") (pintype "bidirectional"))
      (node (ref "D5") (pin "1") (pinfunction "K_1") (pintype "bidirectional"))
      (node (ref "EPD_C11") (pin "1") (pinfunction "1_1") (pintype "passive"))
      (node (ref "J1") (pin "23") (pinfunction "23_23") (pintype "bidirectional"))
    )
    (net (code "39") (name "RESE") (class "Default")
      (node (ref "J1") (pin "3") (pinfunction "3_3") (pintype "bidirectional"))
      (node (ref "Q3") (pin "2") (pinfunction "S_2") (pintype "bidirectional"))
      (node (ref "R3") (pin "1") (pinfunction "1_1") (pintype "passive"))
    )
    (net (code "40") (name "RESE'") (class "Default")
      (node (ref "R2") (pin "2") (pinfunction "2_2") (pintype "passive"))
      (node (ref "R3") (pin "2") (pinfunction "2_2") (pintype "passive"))
      (node (ref "SJ1") (pin "2") (pinfunction "2_2") (pintype "passive"))
    )
    (net (code "41") (name "RESET") (class "Default")
      (node (ref "C5") (pin "1") (pinfunction "1_1") (pintype "passive"))
      (node (ref "IC1") (pin "1") (pinfunction "VOUT_1") (pintype "bidirectional"))
      (node (ref "RESET_BUTTON") (pin "3") (pinfunction "3_3") (pintype "passive"))
      (node (ref "RESET_BUTTON") (pin "4") (pinfunction "4_4") (pintype "passive"))
      (node (ref "R_RESET") (pin "2") (pinfunction "2_2") (pintype "passive"))
      (node (ref "U2") (pin "3") (pinfunction "EN_3") (pintype "input"))
    )
    (net (code "42") (name "RTC_RST") (class "Default")
      (node (ref "U2") (pin "16") (pinfunction "IO18_16") (pintype "bidirectional"))
      (node (ref "U3") (pin "4") (pinfunction "~{RST}_4") (pintype "input"))
    )
    (net (code "43") (name "RX") (class "Default")
      (node (ref "TP2") (pin "TP") (pinfunction "TP_TP") (pintype "input"))
      (node (ref "U2") (pin "24") (pinfunction "RXD0/GPIO17_24") (pintype "bidirectional"))
    )
    (net (code "44") (name "SCK") (class "Default")
      (node (ref "D10") (pin "1") (pinfunction "1_1") (pintype "passive"))
      (node (ref "J1") (pin "13") (pinfunction "13_13") (pintype "bidirectional"))
      (node (ref "J4") (pin "P5") (pinfunction "CLK_P5") (pintype "bidirectional"))
      (node (ref "R6") (pin "1") (pinfunction "1_1") (pintype "passive"))
      (node (ref "TP8") (pin "TP") (pinfunction "TP_TP") (pintype "input"))
      (node (ref "U1") (pin "6") (pinfunction "CLK_6") (pintype "input"))
      (node (ref "U2") (pin "6") (pinfunction "IO6_6") (pintype "bidirectional"))
    )
    (net (code "45") (name "SCL") (class "Default")
      (node (ref "J3") (pin "4") (pinfunction "4_4") (pintype "passive"))
      (node (ref "R2-PINH") (pin "1") (pinfunction "1_1") (pintype "passive"))
      (node (ref "SENSOR2") (pin "4") (pinfunction "SCK_4") (pintype "input"))
      (node (ref "U2") (pin "20") (pinfunction "IO22_20") (pintype "bidirectional"))
      (node (ref "U3") (pin "16") (pinfunction "SCL_16") (pintype "input"))
      (node (ref "U4") (pin "7") (pinfunction "SCL_7") (pintype "input"))
    )
    (net (code "46") (name "SDA") (class "Default")
      (node (ref "J3") (pin "3") (pinfunction "3_3") (pintype "passive"))
      (node (ref "R1_PINH") (pin "1") (pinfunction "1_1") (pintype "passive"))
      (node (ref "SENSOR2") (pin "3") (pinfunction "SDI_3") (pintype "bidirectional"))
      (node (ref "U2") (pin "19") (pinfunction "IO21_19") (pintype "bidirectional"))
      (node (ref "U3") (pin "15") (pinfunction "SDA_15") (pintype "bidirectional"))
      (node (ref "U4") (pin "8") (pinfunction "SDA_8") (pintype "bidirectional"))
    )
    (net (code "47") (name "SRC") (class "Default")
      (node (ref "C4") (pin "2") (pinfunction "2_2") (pintype "passive"))
      (node (ref "D5") (pin "2") (pinfunction "A_2") (pintype "bidirectional"))
      (node (ref "L1") (pin "1") (pinfunction "1_1") (pintype "passive"))
      (node (ref "Q3") (pin "3") (pinfunction "D_3") (pintype "bidirectional"))
    )
    (net (code "48") (name "SS_SD") (class "Default")
      (node (ref "D8") (pin "1") (pinfunction "1_1") (pintype "passive"))
      (node (ref "J4") (pin "P2") (pinfunction "CD/DAT3_P2") (pintype "bidirectional"))
      (node (ref "R10") (pin "1") (pinfunction "1_1") (pintype "passive"))
      (node (ref "U2") (pin "4") (pinfunction "IO4_4") (pintype "bidirectional"))
    )
    (net (code "49") (name "TX") (class "Default")
      (node (ref "TP1") (pin "TP") (pinfunction "TP_TP") (pintype "input"))
      (node (ref "U2") (pin "25") (pinfunction "TXD0/GPIO16_25") (pintype "bidirectional"))
    )
    (net (code "50") (name "USB_D+") (class "Default")
      (node (ref "D1") (pin "1") (pinfunction "I/O1_1_1") (pintype "bidirectional"))
      (node (ref "U2") (pin "14") (pinfunction "IO13_14") (pintype "bidirectional"))
    )
    (net (code "51") (name "USB_D-") (class "Default")
      (node (ref "D1") (pin "3") (pinfunction "I/O2_1_3") (pintype "bidirectional"))
      (node (ref "U2") (pin "13") (pinfunction "IO12_13") (pintype "bidirectional"))
    )
    (net (code "52") (name "VBAT") (class "Default")
      (node (ref "C2_BAT") (pin "1") (pinfunction "1_1") (pintype "passive"))
      (node (ref "MCP73831") (pin "3") (pinfunction "VBAT_3") (pintype "power_in"))
      (node (ref "Q1") (pin "3") (pinfunction "D_3") (pintype "bidirectional"))
      (node (ref "TP3") (pin "TP") (pinfunction "TP_TP") (pintype "input"))
      (node (ref "U4") (pin "2") (pinfunction "CELL_2") (pintype "power_in"))
      (node (ref "U4") (pin "3") (pinfunction "VDD_3") (pintype "power_in"))
    )
    (net (code "53") (name "VBUS") (class "Default")
      (node (ref "C1_BAT") (pin "1") (pinfunction "1_1") (pintype "passive"))
      (node (ref "C4_USB") (pin "1") (pinfunction "1_1") (pintype "passive"))
      (node (ref "C5_USB") (pin "1") (pinfunction "1_1") (pintype "passive"))
      (node (ref "CHG_LED") (pin "A") (pinfunction "A_A") (pintype "passive"))
      (node (ref "D1") (pin "5") (pinfunction "VBUS_5") (pintype "bidirectional"))
      (node (ref "D2") (pin "2") (pinfunction "ANODE_2") (pintype "bidirectional"))
      (node (ref "MCP73831") (pin "4") (pinfunction "VIN_4") (pintype "power_in"))
      (node (ref "PFMF.050.1") (pin "2") (pinfunction "2_2") (pintype "passive"))
      (node (ref "Q1") (pin "1") (pinfunction "G_1") (pintype "bidirectional"))
      (node (ref "R1_PWRUSB") (pin "2") (pinfunction "2_2") (pintype "passive"))
      (node (ref "TP14") (pin "TP") (pinfunction "TP_TP") (pintype "input"))
    )
    (net (code "54") (name "VRTC") (class "Default")
      (node (ref "C10_SUPERCAP") (pin "2") (pinfunction "2_2") (pintype "passive"))
      (node (ref "C8") (pin "1") (pinfunction "1_1") (pintype "passive"))
      (node (ref "R_CAPACITOR") (pin "2") (pinfunction "2_2") (pintype "passive"))
      (node (ref "U3") (pin "14") (pinfunction "VBAT_14") (pintype "power_in"))
    )
    (net (code "55") (name "VUSB") (class "Default")
      (node (ref "J2") (pin "A4") (pinfunction "A4_A4") (pintype "bidirectional"))
      (node (ref "J2") (pin "A9") (pinfunction "A9_A9") (pintype "bidirectional"))
      (node (ref "J2") (pin "B4") (pinfunction "B4_B4") (pintype "bidirectional"))
      (node (ref "J2") (pin "B9") (pinfunction "B9_B9") (pintype "bidirectional"))
      (node (ref "PFMF.050.1") (pin "1") (pinfunction "1_1") (pintype "passive"))
    )
    (net (code "56") (name "unconnected-(IC1-NC-Pad4)") (class "Default")
      (node (ref "IC1") (pin "4") (pinfunction "NC_4") (pintype "no_connect"))
    )
    (net (code "57") (name "unconnected-(IC4-NC-Pad4)") (class "Default")
      (node (ref "IC4") (pin "4") (pinfunction "NC_4") (pintype "no_connect"))
    )
    (net (code "58") (name "unconnected-(J1-Pad1)") (class "Default")
      (node (ref "J1") (pin "1") (pinfunction "1_1") (pintype "bidirectional"))
    )
    (net (code "59") (name "unconnected-(J1-Pad6)") (class "Default")
      (node (ref "J1") (pin "6") (pinfunction "6_6") (pintype "bidirectional"))
    )
    (net (code "60") (name "unconnected-(J1-Pad7)") (class "Default")
      (node (ref "J1") (pin "7") (pinfunction "7_7") (pintype "bidirectional"))
    )
    (net (code "61") (name "unconnected-(J2-PadA8)") (class "Default")
      (node (ref "J2") (pin "A8") (pinfunction "A8_A8") (pintype "bidirectional"))
    )
    (net (code "62") (name "unconnected-(J2-PadB8)") (class "Default")
      (node (ref "J2") (pin "B8") (pinfunction "B8_B8") (pintype "bidirectional"))
    )
    (net (code "63") (name "unconnected-(J4-DAT1-PadP8)") (class "Default")
      (node (ref "J4") (pin "P8") (pinfunction "DAT1_P8") (pintype "bidirectional"))
    )
    (net (code "64") (name "unconnected-(J4-DAT2-PadP1)") (class "Default")
      (node (ref "J4") (pin "P1") (pinfunction "DAT2_P1") (pintype "bidirectional"))
    )
    (net (code "65") (name "unconnected-(J4-DETECTION_1-PadS1)") (class "Default")
      (node (ref "J4") (pin "S1") (pinfunction "DETECTION_1_S1") (pintype "bidirectional"))
    )
    (net (code "66") (name "unconnected-(J4-DETECTION_2-PadS2)") (class "Default")
      (node (ref "J4") (pin "S2") (pinfunction "DETECTION_2_S2") (pintype "bidirectional"))
    )
    (net (code "67") (name "unconnected-(U2-NC-Pad22)") (class "Default")
      (node (ref "U2") (pin "22") (pinfunction "NC_22") (pintype "no_connect"))
    )
    (net (code "68") (name "unconnected-(U4-~{ALERT}-Pad5)") (class "Default")
      (node (ref "U4") (pin "5") (pinfunction "~{ALERT}_5") (pintype "output"))
    )
  )
)
